# Digital_Clock_SCH_2_0.net
KiCad netlist of a schematic drawn in Altium Designer
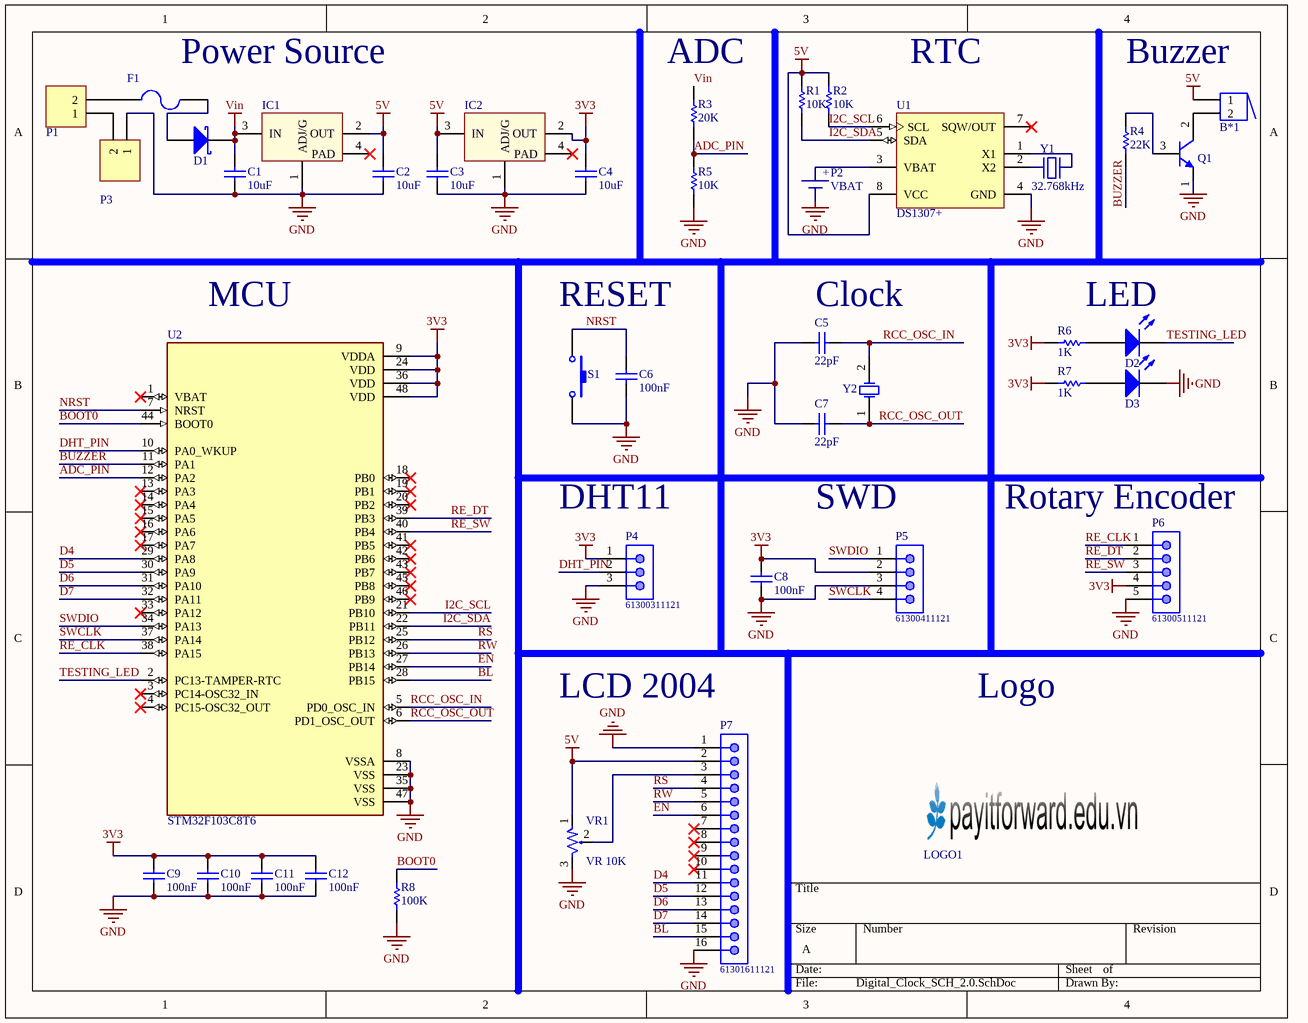
[diagram p0: Digital_Clock_SCH_2.0.SchDoc]

(export (version "E")
  (design (tool "Eeschema 10.0.6"))
  (components
    (comp (ref "B*1") (value "Buzzer") (footprint "BUZZER") (libsource (lib "PIF_Library") (part "Buzzer")))
    (comp (ref "C1")
      (value "10uF")
      (footprint "CAP-SM-0805")
      (description "Capacitor")
      (fields (field (name "Comment") "Cap Non-Pol SMD"))
      (libsource (lib "PIF_Library") (part "Cap Non-Pol SMD"))
    )
    (comp (ref "C2")
      (value "10uF")
      (footprint "CAP-SM-0805")
      (description "Capacitor")
      (fields (field (name "Comment") "Cap Non-Pol SMD"))
      (libsource (lib "PIF_Library") (part "Cap Non-Pol SMD"))
    )
    (comp (ref "C3")
      (value "10uF")
      (footprint "CAP-SM-0805")
      (description "Capacitor")
      (fields (field (name "Comment") "Cap Non-Pol SMD"))
      (libsource (lib "PIF_Library") (part "Cap Non-Pol SMD"))
    )
    (comp (ref "C4")
      (value "10uF")
      (footprint "CAP-SM-0805")
      (description "Capacitor")
      (fields (field (name "Comment") "Cap Non-Pol SMD"))
      (libsource (lib "PIF_Library") (part "Cap Non-Pol SMD"))
    )
    (comp (ref "C5")
      (value "22pF")
      (footprint "CAP-SM-0603")
      (description "Capacitor")
      (fields (field (name "Comment") "Cap Non-Pol SMD"))
      (libsource (lib "PIF_Library") (part "Cap Non-Pol SMD"))
    )
    (comp (ref "C6")
      (value "100nF")
      (footprint "CAP-SM-0603")
      (description "Capacitor")
      (fields (field (name "Comment") "Cap Non-Pol SMD"))
      (libsource (lib "PIF_Library") (part "Cap Non-Pol SMD"))
    )
    (comp (ref "C7")
      (value "22pF")
      (footprint "CAP-SM-0603")
      (description "Capacitor")
      (fields (field (name "Comment") "Cap Non-Pol SMD"))
      (libsource (lib "PIF_Library") (part "Cap Non-Pol SMD"))
    )
    (comp (ref "C8")
      (value "100nF")
      (footprint "CAP-SM-0603")
      (description "Capacitor")
      (fields (field (name "Comment") "Cap Non-Pol SMD"))
      (libsource (lib "PIF_Library") (part "Cap Non-Pol SMD"))
    )
    (comp (ref "C9")
      (value "100nF")
      (footprint "CAP-SM-0603")
      (description "Capacitor")
      (fields (field (name "Comment") "Cap Non-Pol SMD"))
      (libsource (lib "PIF_Library") (part "Cap Non-Pol SMD"))
    )
    (comp (ref "C10")
      (value "100nF")
      (footprint "CAP-SM-0603")
      (description "Capacitor")
      (fields (field (name "Comment") "Cap Non-Pol SMD"))
      (libsource (lib "PIF_Library") (part "Cap Non-Pol SMD"))
    )
    (comp (ref "C11")
      (value "100nF")
      (footprint "CAP-SM-0603")
      (description "Capacitor")
      (fields (field (name "Comment") "Cap Non-Pol SMD"))
      (libsource (lib "PIF_Library") (part "Cap Non-Pol SMD"))
    )
    (comp (ref "C12")
      (value "100nF")
      (footprint "CAP-SM-0603")
      (description "Capacitor")
      (fields (field (name "Comment") "Cap Non-Pol SMD"))
      (libsource (lib "PIF_Library") (part "Cap Non-Pol SMD"))
    )
    (comp (ref "D1")
      (value "D Schottky")
      (footprint "SS34")
      (description "Schottky Diode")
      (fields (field (name "PUBLISHER") "Altium Limited"))
      (libsource (lib "PIF_Library") (part "D Schottky"))
    )
    (comp (ref "D2")
      (value "LED SMD")
      (footprint "LED_0805_Blue")
      (description "LED")
      (libsource (lib "PIF_Library") (part "LED SMD"))
    )
    (comp (ref "D3")
      (value "LED SMD")
      (footprint "LED_0805_Blue")
      (description "LED")
      (libsource (lib "PIF_Library") (part "LED SMD"))
    )
    (comp (ref "F1") (value "Fuse") (footprint "FUSE SMD") (libsource (lib "PIF_Library") (part "Fuse")))
    (comp (ref "IC1")
      (value "LM1117")
      (footprint "SOT223-4N")
      (description "Available in 1.8V, 2.5V, 2.85V, 3.3V, 5V, and  Adjustable Versions")
      (libsource (lib "PIF_Library") (part "LM1117"))
    )
    (comp (ref "IC2")
      (value "LM1117")
      (footprint "SOT223-4N")
      (description "Available in 1.8V, 2.5V, 2.85V, 3.3V, 5V, and  Adjustable Versions")
      (libsource (lib "PIF_Library") (part "LM1117"))
    )
    (comp (ref "LOGO1")
      (value "LOGO PIF")
      (footprint "PIF LOGO BIG SSTOP")
      (libsource (lib "PIF_Library") (part "LOGO PIF"))
    )
    (comp (ref "P1")
      (value "Domino 2")
      (footprint "DOMINO SMALL 2")
      (description "Domino, 2-Pin")
      (fields (field (name "PUBLISHER") "Altium Limited"))
      (libsource (lib "PIF_Library") (part "Domino 2"))
    )
    (comp (ref "P2")
      (value "VBAT")
      (footprint "VBAT CR2030")
      (description "CR2032")
      (fields
        (field (name "MANUFACTURER") "DANTONA INDUSTRIES")
        (field (name "MANUFACTURER PART NUMBER") "CR2032 SANYO")
      )
      (libsource (lib "DeltaCross_Libs") (part "VBAT CR2032"))
    )
    (comp (ref "P3")
      (value "Domino 2")
      (footprint "DOMINO SMALL 2")
      (description "Domino, 2-Pin")
      (fields (field (name "PUBLISHER") "Altium Limited"))
      (libsource (lib "") (part "Domino 2_1"))
    )
    (comp (ref "P4")
      (value "61300311121")
      (footprint "61300311121")
      (description "WR-PHD Pin Header, THT, pitch 2.54mm, Single Row, Vertical, 3p")
      (fields (field (name "MANUFACTURER") "Wurth Elektronik"))
      (libsource (lib "Altium_WR-PHD (rev20a)") (part "61300311121"))
    )
    (comp (ref "P5")
      (value "61300411121")
      (footprint "61300411121")
      (description "WR-PHD Pin Header, THT, pitch 2.54mm, Single Row, Vertical, 4p")
      (fields (field (name "MANUFACTURER") "Wurth Elektronik"))
      (libsource (lib "Altium_WR-PHD (rev20a)") (part "61300411121"))
    )
    (comp (ref "P6")
      (value "61300511121")
      (footprint "61300511121")
      (description "WR-PHD Pin Header, THT, pitch 2.54mm, Single Row, Vertical, 5p")
      (fields (field (name "MANUFACTURER") "Wurth Elektronik"))
      (libsource (lib "Altium_WR-PHD (rev20a)") (part "61300511121"))
    )
    (comp (ref "P7")
      (value "61301611121")
      (footprint "61301611121")
      (description "WR-PHD Pin Header, THT, pitch 2.54mm, Single Row, Vertical, 16p")
      (fields (field (name "MANUFACTURER") "Wurth Elektronik"))
      (libsource (lib "Altium_WR-PHD (rev20a)") (part "61301611121"))
    )
    (comp (ref "Q1")
      (value "C1815")
      (footprint "SOT23B")
      (description "NPN Bipolar Transistor")
      (libsource (lib "PIF_Library") (part "C1815"))
    )
    (comp (ref "R1")
      (value "10K")
      (footprint "RES-SM-0603")
      (description "Resistor")
      (fields (field (name "Comment") "RESISTOR SMD"))
      (libsource (lib "PIF_Library") (part "RESISTOR SMD"))
    )
    (comp (ref "R2")
      (value "10K")
      (footprint "RES-SM-0603")
      (description "Resistor")
      (fields (field (name "Comment") "RESISTOR SMD"))
      (libsource (lib "PIF_Library") (part "RESISTOR SMD"))
    )
    (comp (ref "R3")
      (value "20K")
      (footprint "RES-SM-0603")
      (description "Resistor")
      (fields (field (name "Comment") "RESISTOR SMD"))
      (libsource (lib "PIF_Library") (part "RESISTOR SMD"))
    )
    (comp (ref "R4")
      (value "22K")
      (footprint "RES-SM-0603")
      (description "Resistor")
      (fields (field (name "Comment") "RESISTOR SMD"))
      (libsource (lib "PIF_Library") (part "RESISTOR SMD"))
    )
    (comp (ref "R5")
      (value "10K")
      (footprint "RES-SM-0603")
      (description "Resistor")
      (fields (field (name "Comment") "RESISTOR SMD"))
      (libsource (lib "PIF_Library") (part "RESISTOR SMD"))
    )
    (comp (ref "R6")
      (value "1K")
      (footprint "RES-SM-0603")
      (description "Resistor")
      (fields (field (name "Comment") "RESISTOR SMD"))
      (libsource (lib "PIF_Library") (part "RESISTOR SMD"))
    )
    (comp (ref "R7")
      (value "1K")
      (footprint "RES-SM-0603")
      (description "Resistor")
      (fields (field (name "Comment") "RESISTOR SMD"))
      (libsource (lib "PIF_Library") (part "RESISTOR SMD"))
    )
    (comp (ref "R8")
      (value "100K")
      (footprint "RES-SM-0603")
      (description "Resistor")
      (fields (field (name "Comment") "RESISTOR SMD"))
      (libsource (lib "PIF_Library") (part "RESISTOR SMD"))
    )
    (comp (ref "S1")
      (value "Tact SW - 2Pin")
      (footprint "SW-SMD")
      (description "Switch button 2 pin")
      (libsource (lib "PIF_Library") (part "Tact SW - 2Pin"))
    )
    (comp (ref "U1")
      (value "DS1307+")
      (footprint "MAXM-P8-1")
      (description "I2C Real-Time Clock, 5 V, 0 to 70 degC, 8-Pin DIP, RoHS, Tube")
      (fields (field (name "MANUFACTURER") "Maxim"))
      (libsource (lib "HCMUT") (part "MAXM-DS1307Z+-8"))
    )
    (comp (ref "U2")
      (value "STM32F103C8T6")
      (footprint "QFP50P900X900X160-48N")
      (libsource (lib "STM32F103C8T6") (part "STM32F103C8T6"))
    )
    (comp (ref "VR1")
      (value "VR 10K")
      (footprint "Varistor 1")
      (description "Var Resistor")
      (fields (field (name "Comment") "10K"))
      (libsource (lib "PIF_Library") (part "Var Resistor"))
    )
    (comp (ref "Y1")
      (value "32.768kHz")
      (footprint "XTAL 32768 3x8")
      (description "Crystal For all Crystal 2pin")
      (libsource (lib "DeltaCross_Libs") (part "XTAL"))
    )
    (comp (ref "Y2")
      (value "XTAL")
      (footprint "XT2")
      (description "Crystal Oscillator")
      (fields (field (name "PUBLISHER") "Altium Limited"))
      (libsource (lib "PIF_Library") (part "XTAL"))
    )
  )
  (nets
    (net (code "1") (name "/ADC_PIN") (class "Default")
      (node (ref "R3") (pin "1") (pinfunction "1_1") (pintype "passive"))
      (node (ref "R5") (pin "2") (pinfunction "2_2") (pintype "passive"))
      (node (ref "U2") (pin "12") (pinfunction "PA2_12") (pintype "bidirectional"))
    )
    (net (code "2") (name "/BL") (class "Default")
      (node (ref "P7") (pin "15") (pinfunction "15_15") (pintype "passive"))
      (node (ref "U2") (pin "28") (pinfunction "PB15_28") (pintype "bidirectional"))
    )
    (net (code "3") (name "/BOOT0") (class "Default")
      (node (ref "R8") (pin "2") (pinfunction "2_2") (pintype "passive"))
      (node (ref "U2") (pin "44") (pinfunction "BOOT0_44") (pintype "input"))
    )
    (net (code "4") (name "/BUZZER") (class "Default")
      (node (ref "R4") (pin "1") (pinfunction "1_1") (pintype "passive"))
      (node (ref "U2") (pin "11") (pinfunction "PA1_11") (pintype "bidirectional"))
    )
    (net (code "5") (name "/D4") (class "Default")
      (node (ref "P7") (pin "11") (pinfunction "11_11") (pintype "passive"))
      (node (ref "U2") (pin "29") (pinfunction "PA8_29") (pintype "bidirectional"))
    )
    (net (code "6") (name "/D5") (class "Default")
      (node (ref "P7") (pin "12") (pinfunction "12_12") (pintype "passive"))
      (node (ref "U2") (pin "30") (pinfunction "PA9_30") (pintype "bidirectional"))
    )
    (net (code "7") (name "/D6") (class "Default")
      (node (ref "P7") (pin "13") (pinfunction "13_13") (pintype "passive"))
      (node (ref "U2") (pin "31") (pinfunction "PA10_31") (pintype "bidirectional"))
    )
    (net (code "8") (name "/D7") (class "Default")
      (node (ref "P7") (pin "14") (pinfunction "14_14") (pintype "passive"))
      (node (ref "U2") (pin "32") (pinfunction "PA11_32") (pintype "bidirectional"))
    )
    (net (code "9") (name "/DHT_PIN") (class "Default")
      (node (ref "P4") (pin "2") (pinfunction "2_2") (pintype "passive"))
      (node (ref "U2") (pin "10") (pinfunction "PA0_WKUP_10") (pintype "bidirectional"))
    )
    (net (code "10") (name "/EN") (class "Default")
      (node (ref "P7") (pin "6") (pinfunction "6_6") (pintype "passive"))
      (node (ref "U2") (pin "27") (pinfunction "PB14_27") (pintype "bidirectional"))
    )
    (net (code "11") (name "/I2C_SCL") (class "Default")
      (node (ref "R2") (pin "1") (pinfunction "1_1") (pintype "passive"))
      (node (ref "U1") (pin "6") (pinfunction "SCL_6") (pintype "input"))
      (node (ref "U2") (pin "21") (pinfunction "PB10_21") (pintype "bidirectional"))
    )
    (net (code "12") (name "/I2C_SDA") (class "Default")
      (node (ref "R1") (pin "1") (pinfunction "1_1") (pintype "passive"))
      (node (ref "U1") (pin "5") (pinfunction "SDA_5") (pintype "bidirectional"))
      (node (ref "U2") (pin "22") (pinfunction "PB11_22") (pintype "bidirectional"))
    )
    (net (code "13") (name "/NRST") (class "Default")
      (node (ref "C6") (pin "2") (pinfunction "2_2") (pintype "passive"))
      (node (ref "S1") (pin "1") (pinfunction "1_1") (pintype "passive"))
      (node (ref "U2") (pin "7") (pinfunction "NRST_7") (pintype "input"))
    )
    (net (code "14") (name "/RCC_OSC_IN") (class "Default")
      (node (ref "C5") (pin "2") (pinfunction "2_2") (pintype "passive"))
      (node (ref "U2") (pin "5") (pinfunction "PD0_OSC_IN_5") (pintype "bidirectional"))
      (node (ref "Y2") (pin "2") (pinfunction "OSC2_2") (pintype "passive"))
    )
    (net (code "15") (name "/RCC_OSC_OUT") (class "Default")
      (node (ref "C7") (pin "1") (pinfunction "1_1") (pintype "passive"))
      (node (ref "U2") (pin "6") (pinfunction "PD1_OSC_OUT_6") (pintype "bidirectional"))
      (node (ref "Y2") (pin "1") (pinfunction "OSC1_1") (pintype "passive"))
    )
    (net (code "16") (name "/RE_CLK") (class "Default")
      (node (ref "P6") (pin "1") (pinfunction "1_1") (pintype "passive"))
      (node (ref "U2") (pin "38") (pinfunction "PA15_38") (pintype "bidirectional"))
    )
    (net (code "17") (name "/RE_DT") (class "Default")
      (node (ref "P6") (pin "2") (pinfunction "2_2") (pintype "passive"))
      (node (ref "U2") (pin "39") (pinfunction "PB3_39") (pintype "bidirectional"))
    )
    (net (code "18") (name "/RE_SW") (class "Default")
      (node (ref "P6") (pin "3") (pinfunction "3_3") (pintype "passive"))
      (node (ref "U2") (pin "40") (pinfunction "PB4_40") (pintype "bidirectional"))
    )
    (net (code "19") (name "/RS") (class "Default")
      (node (ref "P7") (pin "4") (pinfunction "4_4") (pintype "passive"))
      (node (ref "U2") (pin "25") (pinfunction "PB12_25") (pintype "bidirectional"))
    )
    (net (code "20") (name "/RW") (class "Default")
      (node (ref "P7") (pin "5") (pinfunction "5_5") (pintype "passive"))
      (node (ref "U2") (pin "26") (pinfunction "PB13_26") (pintype "bidirectional"))
    )
    (net (code "21") (name "/SWCLK") (class "Default")
      (node (ref "P5") (pin "4") (pinfunction "4_4") (pintype "passive"))
      (node (ref "U2") (pin "37") (pinfunction "PA14_37") (pintype "bidirectional"))
    )
    (net (code "22") (name "/SWDIO") (class "Default")
      (node (ref "P5") (pin "1") (pinfunction "1_1") (pintype "passive"))
      (node (ref "U2") (pin "34") (pinfunction "PA13_34") (pintype "bidirectional"))
    )
    (net (code "23") (name "/TESTING_LED") (class "Default")
      (node (ref "D2") (pin "2") (pinfunction "K_2") (pintype "passive"))
      (node (ref "U2") (pin "2") (pinfunction "PC13-TAMPER-RTC_2") (pintype "bidirectional"))
    )
    (net (code "24") (name "3V3") (class "Default")
      (node (ref "C10") (pin "2") (pinfunction "2_2") (pintype "passive"))
      (node (ref "C11") (pin "2") (pinfunction "2_2") (pintype "passive"))
      (node (ref "C12") (pin "2") (pinfunction "2_2") (pintype "passive"))
      (node (ref "C4") (pin "2") (pinfunction "2_2") (pintype "passive"))
      (node (ref "C8") (pin "2") (pinfunction "2_2") (pintype "passive"))
      (node (ref "C9") (pin "2") (pinfunction "2_2") (pintype "passive"))
      (node (ref "IC2") (pin "2") (pinfunction "OUT_2") (pintype "passive"))
      (node (ref "P4") (pin "1") (pinfunction "1_1") (pintype "passive"))
      (node (ref "P5") (pin "2") (pinfunction "2_2") (pintype "passive"))
      (node (ref "P6") (pin "4") (pinfunction "4_4") (pintype "passive"))
      (node (ref "R6") (pin "1") (pinfunction "1_1") (pintype "passive"))
      (node (ref "R7") (pin "1") (pinfunction "1_1") (pintype "passive"))
      (node (ref "U2") (pin "24") (pinfunction "VDD_24") (pintype "power_in"))
      (node (ref "U2") (pin "36") (pinfunction "VDD_36") (pintype "power_in"))
      (node (ref "U2") (pin "48") (pinfunction "VDD_48") (pintype "power_in"))
      (node (ref "U2") (pin "9") (pinfunction "VDDA_9") (pintype "power_in"))
    )
    (net (code "25") (name "5V") (class "Default")
      (node (ref "B*1") (pin "1") (pinfunction "1_1") (pintype "passive"))
      (node (ref "C2") (pin "2") (pinfunction "2_2") (pintype "passive"))
      (node (ref "C3") (pin "2") (pinfunction "2_2") (pintype "passive"))
      (node (ref "IC1") (pin "2") (pinfunction "OUT_2") (pintype "passive"))
      (node (ref "IC2") (pin "3") (pinfunction "IN_3") (pintype "passive"))
      (node (ref "P7") (pin "2") (pinfunction "2_2") (pintype "passive"))
      (node (ref "R1") (pin "2") (pinfunction "2_2") (pintype "passive"))
      (node (ref "R2") (pin "2") (pinfunction "2_2") (pintype "passive"))
      (node (ref "U1") (pin "8") (pinfunction "VCC_8") (pintype "power_in"))
      (node (ref "VR1") (pin "1") (pinfunction "1_1") (pintype "passive"))
    )
    (net (code "26") (name "GND") (class "Default")
      (node (ref "C1") (pin "1") (pinfunction "1_1") (pintype "passive"))
      (node (ref "C10") (pin "1") (pinfunction "1_1") (pintype "passive"))
      (node (ref "C11") (pin "1") (pinfunction "1_1") (pintype "passive"))
      (node (ref "C12") (pin "1") (pinfunction "1_1") (pintype "passive"))
      (node (ref "C2") (pin "1") (pinfunction "1_1") (pintype "passive"))
      (node (ref "C3") (pin "1") (pinfunction "1_1") (pintype "passive"))
      (node (ref "C4") (pin "1") (pinfunction "1_1") (pintype "passive"))
      (node (ref "C5") (pin "1") (pinfunction "1_1") (pintype "passive"))
      (node (ref "C6") (pin "1") (pinfunction "1_1") (pintype "passive"))
      (node (ref "C7") (pin "2") (pinfunction "2_2") (pintype "passive"))
      (node (ref "C8") (pin "1") (pinfunction "1_1") (pintype "passive"))
      (node (ref "C9") (pin "1") (pinfunction "1_1") (pintype "passive"))
      (node (ref "D3") (pin "2") (pinfunction "K_2") (pintype "passive"))
      (node (ref "IC1") (pin "1") (pinfunction "ADJ/G_1") (pintype "passive"))
      (node (ref "IC2") (pin "1") (pinfunction "ADJ/G_1") (pintype "passive"))
      (node (ref "P2") (pin "2") (pinfunction "+_2") (pintype "passive"))
      (node (ref "P3") (pin "1") (pinfunction "1_1") (pintype "passive"))
      (node (ref "P4") (pin "3") (pinfunction "3_3") (pintype "passive"))
      (node (ref "P5") (pin "3") (pinfunction "3_3") (pintype "passive"))
      (node (ref "P6") (pin "5") (pinfunction "5_5") (pintype "passive"))
      (node (ref "P7") (pin "1") (pinfunction "1_1") (pintype "passive"))
      (node (ref "P7") (pin "16") (pinfunction "16_16") (pintype "passive"))
      (node (ref "Q1") (pin "1") (pinfunction "E_1") (pintype "passive"))
      (node (ref "R5") (pin "1") (pinfunction "1_1") (pintype "passive"))
      (node (ref "R8") (pin "1") (pinfunction "1_1") (pintype "passive"))
      (node (ref "S1") (pin "2") (pinfunction "2_2") (pintype "passive"))
      (node (ref "U1") (pin "4") (pinfunction "GND_4") (pintype "power_in"))
      (node (ref "U2") (pin "23") (pinfunction "VSS_23") (pintype "power_in"))
      (node (ref "U2") (pin "35") (pinfunction "VSS_35") (pintype "power_in"))
      (node (ref "U2") (pin "47") (pinfunction "VSS_47") (pintype "power_in"))
      (node (ref "U2") (pin "8") (pinfunction "VSSA_8") (pintype "power_in"))
      (node (ref "VR1") (pin "3") (pinfunction "3_3") (pintype "passive"))
    )
    (net (code "27") (name "Net-(D1-A)") (class "Default")
      (node (ref "D1") (pin "1") (pinfunction "A_1") (pintype "passive"))
      (node (ref "F1") (pin "1") (pinfunction "1_1") (pintype "passive"))
    )
    (net (code "28") (name "Net-(D2-A)") (class "Default")
      (node (ref "D2") (pin "1") (pinfunction "A_1") (pintype "passive"))
      (node (ref "R6") (pin "2") (pinfunction "2_2") (pintype "passive"))
    )
    (net (code "29") (name "Net-(D3-A)") (class "Default")
      (node (ref "D3") (pin "1") (pinfunction "A_1") (pintype "passive"))
      (node (ref "R7") (pin "2") (pinfunction "2_2") (pintype "passive"))
    )
    (net (code "30") (name "Net-(F1-Pad2)") (class "Default")
      (node (ref "F1") (pin "2") (pinfunction "2_2") (pintype "passive"))
      (node (ref "P1") (pin "2") (pinfunction "2_2") (pintype "passive"))
    )
    (net (code "31") (name "Net-(P1-Pad1)") (class "Default")
      (node (ref "P1") (pin "1") (pinfunction "1_1") (pintype "passive"))
      (node (ref "P3") (pin "2") (pinfunction "2_2") (pintype "passive"))
    )
    (net (code "32") (name "Net-(P7-Pad3)") (class "Default")
      (node (ref "P7") (pin "3") (pinfunction "3_3") (pintype "passive"))
      (node (ref "VR1") (pin "2") (pinfunction "2_2") (pintype "passive"))
    )
    (net (code "33") (name "Net-(Q1-B)") (class "Default")
      (node (ref "Q1") (pin "3") (pinfunction "B_3") (pintype "passive"))
      (node (ref "R4") (pin "2") (pinfunction "2_2") (pintype "passive"))
    )
    (net (code "34") (name "Net-(Q1-C)") (class "Default")
      (node (ref "B*1") (pin "2") (pinfunction "2_2") (pintype "passive"))
      (node (ref "Q1") (pin "2") (pinfunction "C_2") (pintype "passive"))
    )
    (net (code "35") (name "Net-(U1-VBAT)") (class "Default")
      (node (ref "P2") (pin "1") (pinfunction "+_1") (pintype "passive"))
      (node (ref "U1") (pin "3") (pinfunction "VBAT_3") (pintype "power_in"))
    )
    (net (code "36") (name "Net-(U1-X1)") (class "Default")
      (node (ref "U1") (pin "1") (pinfunction "X1_1") (pintype "passive"))
      (node (ref "Y1") (pin "2") (pinfunction "2_2") (pintype "passive"))
    )
    (net (code "37") (name "Net-(U1-X2)") (class "Default")
      (node (ref "U1") (pin "2") (pinfunction "X2_2") (pintype "passive"))
      (node (ref "Y1") (pin "1") (pinfunction "1_1") (pintype "passive"))
    )
    (net (code "38") (name "Vin") (class "Default")
      (node (ref "C1") (pin "2") (pinfunction "2_2") (pintype "passive"))
      (node (ref "D1") (pin "2") (pinfunction "K_2") (pintype "passive"))
      (node (ref "IC1") (pin "3") (pinfunction "IN_3") (pintype "passive"))
      (node (ref "R3") (pin "2") (pinfunction "2_2") (pintype "passive"))
    )
    (net (code "39") (name "unconnected-(IC1-PAD-Pad4)") (class "Default")
      (node (ref "IC1") (pin "4") (pinfunction "PAD_4") (pintype "passive+no_connect"))
    )
    (net (code "40") (name "unconnected-(IC2-PAD-Pad4)") (class "Default")
      (node (ref "IC2") (pin "4") (pinfunction "PAD_4") (pintype "passive+no_connect"))
    )
    (net (code "41") (name "unconnected-(P7-Pad7)") (class "Default")
      (node (ref "P7") (pin "7") (pinfunction "7_7") (pintype "passive+no_connect"))
    )
    (net (code "42") (name "unconnected-(P7-Pad8)") (class "Default")
      (node (ref "P7") (pin "8") (pinfunction "8_8") (pintype "passive+no_connect"))
    )
    (net (code "43") (name "unconnected-(P7-Pad9)") (class "Default")
      (node (ref "P7") (pin "9") (pinfunction "9_9") (pintype "passive+no_connect"))
    )
    (net (code "44") (name "unconnected-(P7-Pad10)") (class "Default")
      (node (ref "P7") (pin "10") (pinfunction "10_10") (pintype "passive+no_connect"))
    )
    (net (code "45") (name "unconnected-(U1-SQW{slash}OUT-Pad7)") (class "Default")
      (node (ref "U1") (pin "7") (pinfunction "SQW/OUT_7") (pintype "open_collector+no_connect"))
    )
    (net (code "46") (name "unconnected-(U2-PA3-Pad13)") (class "Default")
      (node (ref "U2") (pin "13") (pinfunction "PA3_13") (pintype "bidirectional+no_connect"))
    )
    (net (code "47") (name "unconnected-(U2-PA4-Pad14)") (class "Default")
      (node (ref "U2") (pin "14") (pinfunction "PA4_14") (pintype "bidirectional+no_connect"))
    )
    (net (code "48") (name "unconnected-(U2-PA5-Pad15)") (class "Default")
      (node (ref "U2") (pin "15") (pinfunction "PA5_15") (pintype "bidirectional+no_connect"))
    )
    (net (code "49") (name "unconnected-(U2-PA6-Pad16)") (class "Default")
      (node (ref "U2") (pin "16") (pinfunction "PA6_16") (pintype "bidirectional+no_connect"))
    )
    (net (code "50") (name "unconnected-(U2-PA7-Pad17)") (class "Default")
      (node (ref "U2") (pin "17") (pinfunction "PA7_17") (pintype "bidirectional+no_connect"))
    )
    (net (code "51") (name "unconnected-(U2-PA12-Pad33)") (class "Default")
      (node (ref "U2") (pin "33") (pinfunction "PA12_33") (pintype "bidirectional+no_connect"))
    )
    (net (code "52") (name "unconnected-(U2-PB0-Pad18)") (class "Default")
      (node (ref "U2") (pin "18") (pinfunction "PB0_18") (pintype "bidirectional+no_connect"))
    )
    (net (code "53") (name "unconnected-(U2-PB1-Pad19)") (class "Default")
      (node (ref "U2") (pin "19") (pinfunction "PB1_19") (pintype "bidirectional+no_connect"))
    )
    (net (code "54") (name "unconnected-(U2-PB2-Pad20)") (class "Default")
      (node (ref "U2") (pin "20") (pinfunction "PB2_20") (pintype "bidirectional+no_connect"))
    )
    (net (code "55") (name "unconnected-(U2-PB5-Pad41)") (class "Default")
      (node (ref "U2") (pin "41") (pinfunction "PB5_41") (pintype "bidirectional+no_connect"))
    )
    (net (code "56") (name "unconnected-(U2-PB6-Pad42)") (class "Default")
      (node (ref "U2") (pin "42") (pinfunction "PB6_42") (pintype "bidirectional+no_connect"))
    )
    (net (code "57") (name "unconnected-(U2-PB7-Pad43)") (class "Default")
      (node (ref "U2") (pin "43") (pinfunction "PB7_43") (pintype "bidirectional+no_connect"))
    )
    (net (code "58") (name "unconnected-(U2-PB8-Pad45)") (class "Default")
      (node (ref "U2") (pin "45") (pinfunction "PB8_45") (pintype "bidirectional+no_connect"))
    )
    (net (code "59") (name "unconnected-(U2-PB9-Pad46)") (class "Default")
      (node (ref "U2") (pin "46") (pinfunction "PB9_46") (pintype "bidirectional+no_connect"))
    )
    (net (code "60") (name "unconnected-(U2-PC14-OSC32_IN-Pad3)") (class "Default")
      (node (ref "U2") (pin "3") (pinfunction "PC14-OSC32_IN_3") (pintype "bidirectional+no_connect"))
    )
    (net (code "61") (name "unconnected-(U2-PC15-OSC32_OUT-Pad4)") (class "Default")
      (node (ref "U2") (pin "4") (pinfunction "PC15-OSC32_OUT_4") (pintype "bidirectional+no_connect"))
    )
    (net (code "62") (name "unconnected-(U2-VBAT-Pad1)") (class "Default")
      (node (ref "U2") (pin "1") (pinfunction "VBAT_1") (pintype "bidirectional+no_connect"))
    )
  )
)
